# Thermostat.net
KiCad netlist of a schematic drawn in EAGLE
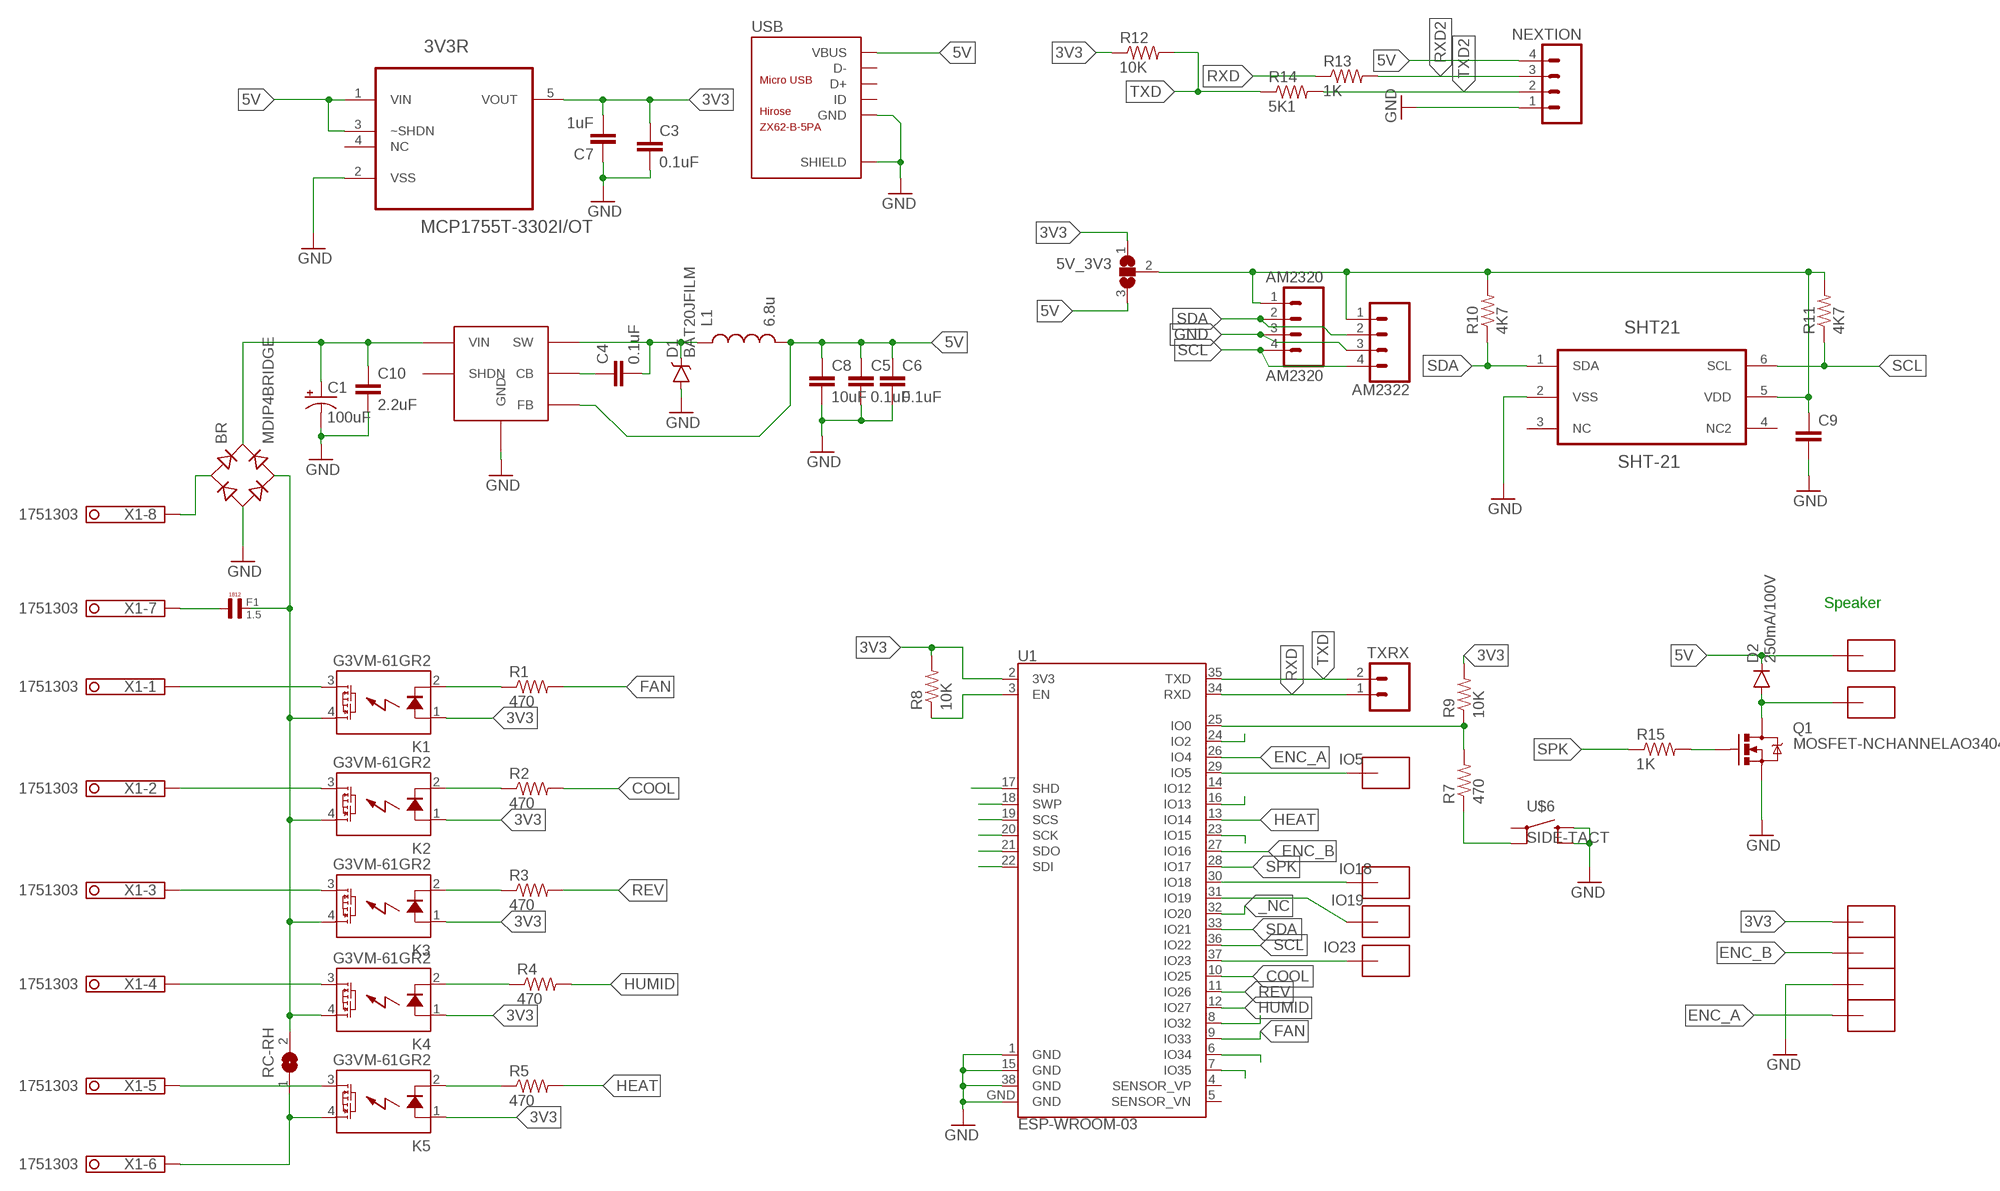
[diagram p0: schematic, sheet 1]

(export (version "E")
  (design (tool "Eeschema 10.0.6"))
  (components
    (comp (ref "3V3R")
      (value "MCP1755T-3302I/OT")
      (footprint "eagle-import:SOT95P270X145-5N")
      (fields (field (name "MPN") "MCP1801T-3302I/OT"))
      (libsource (lib "eagle-import") (part "MCP1801T-3302I/OT"))
    )
    (comp (ref "5V_3V3")
      (value "SJ2W")
      (footprint "eagle-import:SJ_2")
      (libsource (lib "eagle-import") (part "SJ2W"))
    )
    (comp (ref "AM2320")
      (value "AM2320")
      (footprint "eagle-import:1X04")
      (libsource (lib "eagle-import") (part "M04PTH"))
    )
    (comp (ref "AM2322")
      (value "CONN_041.27MM")
      (footprint "eagle-import:1X04_1.27MM")
      (libsource (lib "eagle-import") (part "CONN_041.27MM"))
    )
    (comp (ref "BR")
      (value "MDIP4BRIDGE")
      (footprint "eagle-import:MICRODIP4")
      (libsource (lib "eagle-import") (part "MDIP4BRIDGE"))
    )
    (comp (ref "C1")
      (value "100uF")
      (footprint "eagle-import:PANASONIC_C")
      (libsource (lib "eagle-import") (part "CAP_POLC"))
    )
    (comp (ref "C3")
      (value "0.1uF")
      (footprint "eagle-import:0805")
      (libsource (lib "eagle-import") (part "CAP0805"))
    )
    (comp (ref "C4")
      (value "0.1uF")
      (footprint "eagle-import:0805")
      (libsource (lib "eagle-import") (part "CAP0805"))
    )
    (comp (ref "C5")
      (value "0.1uF")
      (footprint "eagle-import:0805")
      (libsource (lib "eagle-import") (part "CAP0805"))
    )
    (comp (ref "C6")
      (value "0.1uF")
      (footprint "eagle-import:0805")
      (libsource (lib "eagle-import") (part "CAP0805"))
    )
    (comp (ref "C7")
      (value "1uF")
      (footprint "eagle-import:0805")
      (libsource (lib "eagle-import") (part "CAP0805"))
    )
    (comp (ref "C8")
      (value "10uF")
      (footprint "eagle-import:0805")
      (libsource (lib "eagle-import") (part "CAP0805"))
    )
    (comp (ref "C9")
      (value "CAP0603-CAP")
      (footprint "eagle-import:0603-CAP")
      (libsource (lib "eagle-import") (part "CAP0603-CAP"))
    )
    (comp (ref "C10")
      (value "2.2uF")
      (footprint "eagle-import:0805")
      (libsource (lib "eagle-import") (part "CAP0805"))
    )
    (comp (ref "D1")
      (value "BAT20JFILM")
      (footprint "eagle-import:SOD-323")
      (libsource (lib "eagle-import") (part "BAT20JFILM"))
    )
    (comp (ref "D2")
      (value "250mA/100V")
      (footprint "eagle-import:SOD-323")
      (libsource (lib "eagle-import") (part "DIODEBAS16"))
    )
    (comp (ref "F1")
      (value "1.5")
      (footprint "eagle-import:L4,8")
      (libsource (lib "eagle-import") (part "0,1µF"))
    )
    (comp (ref "K1")
      (value "G3VM-61GR2")
      (footprint "eagle-import:SOP04")
      (libsource (lib "eagle-import") (part "AQYSOP22"))
    )
    (comp (ref "K2")
      (value "G3VM-61GR2")
      (footprint "eagle-import:SOP04")
      (libsource (lib "eagle-import") (part "AQYSOP22"))
    )
    (comp (ref "K3")
      (value "G3VM-61GR2")
      (footprint "eagle-import:SOP04")
      (libsource (lib "eagle-import") (part "AQYSOP22"))
    )
    (comp (ref "K4")
      (value "G3VM-61GR2")
      (footprint "eagle-import:SOP04")
      (libsource (lib "eagle-import") (part "AQYSOP22"))
    )
    (comp (ref "K5")
      (value "G3VM-61GR2")
      (footprint "eagle-import:SOP04")
      (libsource (lib "eagle-import") (part "AQYSOP22"))
    )
    (comp (ref "L1")
      (value "6.8u")
      (footprint "eagle-import:1007")
      (libsource (lib "eagle-import") (part "INDUCTOR1007"))
    )
    (comp (ref "NEXTION")
      (value "M04PTH")
      (footprint "eagle-import:1X04")
      (libsource (lib "eagle-import") (part "M04PTH"))
    )
    (comp (ref "Q1")
      (value "MOSFET-NCHANNELAO3404A")
      (footprint "eagle-import:SOT23-3")
      (libsource (lib "eagle-import") (part "MOSFET-NCHANNELAO3404A"))
    )
    (comp (ref "R1")
      (value "470")
      (footprint "eagle-import:0805")
      (libsource (lib "eagle-import") (part "RESISTOR0805-RES"))
    )
    (comp (ref "R2")
      (value "470")
      (footprint "eagle-import:0805")
      (libsource (lib "eagle-import") (part "RESISTOR0805-RES"))
    )
    (comp (ref "R3")
      (value "470")
      (footprint "eagle-import:0805")
      (libsource (lib "eagle-import") (part "RESISTOR0805-RES"))
    )
    (comp (ref "R4")
      (value "470")
      (footprint "eagle-import:0805")
      (libsource (lib "eagle-import") (part "RESISTOR0805-RES"))
    )
    (comp (ref "R5")
      (value "470")
      (footprint "eagle-import:0805")
      (libsource (lib "eagle-import") (part "RESISTOR0805-RES"))
    )
    (comp (ref "R7")
      (value "470")
      (footprint "eagle-import:0805")
      (libsource (lib "eagle-import") (part "SparkFun-Resistors_RESISTOR0805-RES"))
    )
    (comp (ref "R8")
      (value "10K")
      (footprint "eagle-import:0805")
      (libsource (lib "eagle-import") (part "SparkFun-Resistors_RESISTOR0805-RES"))
    )
    (comp (ref "R9")
      (value "10K")
      (footprint "eagle-import:0805")
      (libsource (lib "eagle-import") (part "RESISTOR0805-RES"))
    )
    (comp (ref "R10")
      (value "4K7")
      (footprint "eagle-import:0805")
      (libsource (lib "eagle-import") (part "SparkFun-Resistors_RESISTOR0805-RES"))
    )
    (comp (ref "R11")
      (value "4K7")
      (footprint "eagle-import:0805")
      (libsource (lib "eagle-import") (part "SparkFun-Resistors_RESISTOR0805-RES"))
    )
    (comp (ref "R12")
      (value "10K")
      (footprint "eagle-import:0805")
      (libsource (lib "eagle-import") (part "SparkFun-Resistors_RESISTOR0805-RES"))
    )
    (comp (ref "R13")
      (value "1K")
      (footprint "eagle-import:0805")
      (libsource (lib "eagle-import") (part "SparkFun-Resistors_RESISTOR0805-RES"))
    )
    (comp (ref "R14")
      (value "5K1")
      (footprint "eagle-import:0805")
      (libsource (lib "eagle-import") (part "SparkFun-Resistors_RESISTOR0805-RES"))
    )
    (comp (ref "R15")
      (value "1K")
      (footprint "eagle-import:0805")
      (libsource (lib "eagle-import") (part "SparkFun-Resistors_RESISTOR0805-RES"))
    )
    (comp (ref "RC-RH")
      (value "SJ")
      (footprint "eagle-import:SJ")
      (libsource (lib "eagle-import") (part "SJ"))
    )
    (comp (ref "SHT21")
      (value "SHT-21")
      (footprint "eagle-import:SHT21")
      (libsource (lib "eagle-import") (part "SHT-21"))
    )
    (comp (ref "TXRX")
      (value "M02PTH")
      (footprint "eagle-import:1X02")
      (libsource (lib "eagle-import") (part "M02PTH"))
    )
    (comp (ref "U$1")
      (value "SMD-PAD182X64")
      (footprint "eagle-import:SMD-PAD1")
      (libsource (lib "eagle-import") (part "SMD-PAD182X64"))
    )
    (comp (ref "U$2")
      (value "SMD-PAD182X64")
      (footprint "eagle-import:SMD-PAD1")
      (libsource (lib "eagle-import") (part "SMD-PAD182X64"))
    )
    (comp (ref "U$3")
      (value "SMD-PAD182X64")
      (footprint "eagle-import:SMD-PAD1")
      (libsource (lib "eagle-import") (part "SMD-PAD182X64"))
    )
    (comp (ref "U$4")
      (value "SMD-PAD182X64")
      (footprint "eagle-import:SMD-PAD1")
      (libsource (lib "eagle-import") (part "SMD-PAD182X64"))
    )
    (comp (ref "U$5")
      (value "SMD-PAD1SMD-PAD80X32")
      (footprint "eagle-import:SMD-PAD6")
      (libsource (lib "eagle-import") (part "SMD-PAD1SMD-PAD80X32"))
    )
    (comp (ref "U$6")
      (value "SIDE-TACT")
      (footprint "eagle-import:SIDE-TACT")
      (libsource (lib "eagle-import") (part "SIDE-TACT"))
    )
    (comp (ref "U$7")
      (value "SMD-PAD1SMD-PAD80X32")
      (footprint "eagle-import:SMD-PAD6")
      (libsource (lib "eagle-import") (part "SMD-PAD1SMD-PAD80X32"))
    )
    (comp (ref "U$8")
      (value "SMD-PAD1SMD-PAD80X32")
      (footprint "eagle-import:SMD-PAD6")
      (libsource (lib "eagle-import") (part "SMD-PAD1SMD-PAD80X32"))
    )
    (comp (ref "U$9")
      (value "SMD-PAD1SMD-PAD80X32")
      (footprint "eagle-import:SMD-PAD6")
      (libsource (lib "eagle-import") (part "SMD-PAD1SMD-PAD80X32"))
    )
    (comp (ref "U$10")
      (value "SMD-PAD1SMD-PAD80X32")
      (footprint "eagle-import:SMD-PAD6")
      (libsource (lib "eagle-import") (part "SMD-PAD1SMD-PAD80X32"))
    )
    (comp (ref "U$11")
      (value "SMD-PAD1SMD-PAD80X32")
      (footprint "eagle-import:SMD-PAD6")
      (libsource (lib "eagle-import") (part "SMD-PAD1SMD-PAD80X32"))
    )
    (comp (ref "U1")
      (value "ESP-WROOM-03")
      (footprint "eagle-import:ESP-WROOM-03")
      (libsource (lib "eagle-import") (part "ESP-WROOM-03"))
    )
    (comp (ref "USB")
      (value "ZX62-B-5PA")
      (footprint "eagle-import:MICRO-USB5+6P-SMD-0.65-AB")
      (libsource (lib "eagle-import") (part "MICRO-USB-SMD(ZX62-B-5PA)"))
    )
    (comp (ref "VREG")
      (value "LMR16006YQ")
      (footprint "eagle-import:SOT-23-6")
      (libsource (lib "eagle-import") (part "LMR16006YQ"))
    )
    (comp (ref "X1")
      (value "1751303")
      (footprint "eagle-import:1751303")
      (libsource (lib "eagle-import") (part "1751303"))
    )
  )
  (nets
    (net (code "1") (name "/IO5") (class "Default")
      (node (ref "U$3") (pin ">PAD") (pinfunction "P$1_>PAD") (pintype "bidirectional"))
      (node (ref "U1") (pin "29") (pinfunction "IO5_29") (pintype "bidirectional"))
    )
    (net (code "2") (name "/IO18") (class "Default")
      (node (ref "U$4") (pin ">PAD") (pinfunction "P$1_>PAD") (pintype "bidirectional"))
      (node (ref "U1") (pin "30") (pinfunction "IO18_30") (pintype "bidirectional"))
    )
    (net (code "3") (name "/IO19") (class "Default")
      (node (ref "U$1") (pin ">PAD") (pinfunction "P$1_>PAD") (pintype "bidirectional"))
      (node (ref "U1") (pin "31") (pinfunction "IO19_31") (pintype "bidirectional"))
    )
    (net (code "4") (name "/IO23") (class "Default")
      (node (ref "U$2") (pin ">PAD") (pinfunction "P$1_>PAD") (pintype "bidirectional"))
      (node (ref "U1") (pin "37") (pinfunction "IO23_37") (pintype "bidirectional"))
    )
    (net (code "5") (name "/NC") (class "Default")
      (node (ref "SHT21") (pin "3") (pinfunction "NC_3") (pintype "power_in"))
    )
    (net (code "6") (name "3V3") (class "Default")
      (node (ref "3V3R") (pin "5") (pinfunction "VOUT_5") (pintype "output"))
      (node (ref "5V_3V3") (pin "1") (pinfunction "1_1") (pintype "passive"))
      (node (ref "C3") (pin "1") (pinfunction "1_1") (pintype "passive"))
      (node (ref "C7") (pin "2") (pinfunction "2_2") (pintype "passive"))
      (node (ref "K1") (pin "1") (pinfunction "A_1") (pintype "passive"))
      (node (ref "K2") (pin "1") (pinfunction "A_1") (pintype "passive"))
      (node (ref "K3") (pin "1") (pinfunction "A_1") (pintype "passive"))
      (node (ref "K4") (pin "1") (pinfunction "A_1") (pintype "passive"))
      (node (ref "K5") (pin "1") (pinfunction "A_1") (pintype "passive"))
      (node (ref "R12") (pin "1") (pinfunction "1_1") (pintype "passive"))
      (node (ref "R8") (pin "2") (pinfunction "2_2") (pintype "passive"))
      (node (ref "R9") (pin "2") (pinfunction "2_2") (pintype "passive"))
      (node (ref "U$7") (pin ">PAD") (pinfunction "P$1_>PAD") (pintype "bidirectional"))
      (node (ref "U1") (pin "2") (pinfunction "3V3_2") (pintype "bidirectional"))
    )
    (net (code "7") (name "5V") (class "Default")
      (node (ref "3V3R") (pin "1") (pinfunction "VIN_1") (pintype "power_in"))
      (node (ref "3V3R") (pin "3") (pinfunction "~{SHDN}_3") (pintype "input"))
      (node (ref "5V_3V3") (pin "3") (pinfunction "3_3") (pintype "passive"))
      (node (ref "C5") (pin "1") (pinfunction "1_1") (pintype "passive"))
      (node (ref "C6") (pin "1") (pinfunction "1_1") (pintype "passive"))
      (node (ref "C8") (pin "1") (pinfunction "1_1") (pintype "passive"))
      (node (ref "D2") (pin "C") (pinfunction "C_C") (pintype "passive"))
      (node (ref "L1") (pin "2") (pinfunction "2_2") (pintype "passive"))
      (node (ref "NEXTION") (pin "4") (pinfunction "4_4") (pintype "passive"))
      (node (ref "U$5") (pin ">PAD") (pinfunction "P$1_>PAD") (pintype "bidirectional"))
      (node (ref "USB") (pin "1") (pinfunction "VBUS_1") (pintype "power_in"))
      (node (ref "VREG") (pin "3") (pinfunction "FB_3") (pintype "input"))
    )
    (net (code "8") (name "COOL") (class "Default")
      (node (ref "R2") (pin "2") (pinfunction "2_2") (pintype "passive"))
      (node (ref "U1") (pin "10") (pinfunction "IO25_10") (pintype "bidirectional"))
    )
    (net (code "9") (name "ENC_A") (class "Default")
      (node (ref "U$10") (pin ">PAD") (pinfunction "P$1_>PAD") (pintype "bidirectional"))
      (node (ref "U1") (pin "26") (pinfunction "IO4_26") (pintype "bidirectional"))
    )
    (net (code "10") (name "ENC_B") (class "Default")
      (node (ref "U$8") (pin ">PAD") (pinfunction "P$1_>PAD") (pintype "bidirectional"))
      (node (ref "U1") (pin "27") (pinfunction "IO16_27") (pintype "bidirectional"))
    )
    (net (code "11") (name "FAN") (class "Default")
      (node (ref "R1") (pin "2") (pinfunction "2_2") (pintype "passive"))
      (node (ref "U1") (pin "9") (pinfunction "IO33_9") (pintype "bidirectional"))
    )
    (net (code "12") (name "GND") (class "Default")
      (node (ref "3V3R") (pin "2") (pinfunction "VSS_2") (pintype "passive"))
      (node (ref "AM2320") (pin "3") (pinfunction "3_3") (pintype "passive"))
      (node (ref "AM2322") (pin "3") (pinfunction "3_3") (pintype "passive"))
      (node (ref "BR") (pin "-") (pinfunction "-_-") (pintype "passive"))
      (node (ref "C1") (pin "-") (pinfunction "-_-") (pintype "passive"))
      (node (ref "C10") (pin "2") (pinfunction "2_2") (pintype "passive"))
      (node (ref "C3") (pin "2") (pinfunction "2_2") (pintype "passive"))
      (node (ref "C5") (pin "2") (pinfunction "2_2") (pintype "passive"))
      (node (ref "C6") (pin "2") (pinfunction "2_2") (pintype "passive"))
      (node (ref "C7") (pin "1") (pinfunction "1_1") (pintype "passive"))
      (node (ref "C8") (pin "2") (pinfunction "2_2") (pintype "passive"))
      (node (ref "C9") (pin "2") (pinfunction "2_2") (pintype "passive"))
      (node (ref "D1") (pin "A") (pinfunction "A_A") (pintype "passive"))
      (node (ref "NEXTION") (pin "1") (pinfunction "1_1") (pintype "passive"))
      (node (ref "Q1") (pin "2") (pinfunction "S_2") (pintype "passive"))
      (node (ref "SHT21") (pin "2") (pinfunction "VSS_2") (pintype "input"))
      (node (ref "U$6") (pin "3") (pinfunction "2_3") (pintype "passive"))
      (node (ref "U$6") (pin "4") (pinfunction "4_4") (pintype "passive"))
      (node (ref "U$9") (pin ">PAD") (pinfunction "P$1_>PAD") (pintype "bidirectional"))
      (node (ref "U1") (pin "1") (pinfunction "GND_1") (pintype "bidirectional"))
      (node (ref "U1") (pin "15") (pinfunction "GND_15") (pintype "bidirectional"))
      (node (ref "U1") (pin "38") (pinfunction "GND_38") (pintype "bidirectional"))
      (node (ref "U1") (pin "GND") (pinfunction "GND_GND") (pintype "bidirectional"))
      (node (ref "USB") (pin "5") (pinfunction "GND_5") (pintype "power_in"))
      (node (ref "USB") (pin "P1") (pinfunction "SHIELD_P1") (pintype "power_in"))
      (node (ref "USB") (pin "P2") (pinfunction "SHIELD_P2") (pintype "power_in"))
      (node (ref "USB") (pin "P3") (pinfunction "SHIELD_P3") (pintype "power_in"))
      (node (ref "USB") (pin "P4") (pinfunction "SHIELD_P4") (pintype "power_in"))
      (node (ref "USB") (pin "P5") (pinfunction "SHIELD_P5") (pintype "power_in"))
      (node (ref "USB") (pin "P6") (pinfunction "SHIELD_P6") (pintype "power_in"))
      (node (ref "VREG") (pin "2") (pinfunction "GND_2") (pintype "input"))
    )
    (net (code "13") (name "HEAT") (class "Default")
      (node (ref "R5") (pin "2") (pinfunction "2_2") (pintype "passive"))
      (node (ref "U1") (pin "13") (pinfunction "IO14_13") (pintype "bidirectional"))
    )
    (net (code "14") (name "HUMID") (class "Default")
      (node (ref "R4") (pin "2") (pinfunction "2_2") (pintype "passive"))
      (node (ref "U1") (pin "12") (pinfunction "IO27_12") (pintype "bidirectional"))
    )
    (net (code "15") (name "Net-(F1-1)") (class "Default")
      (node (ref "F1") (pin "P$1") (pinfunction "1_P$1") (pintype "passive"))
      (node (ref "X1") (pin "7") (pinfunction "K_7") (pintype "passive"))
    )
    (net (code "16") (name "Net-(F1-2)") (class "Default")
      (node (ref "BR") (pin "AC2") (pinfunction "AC2_AC2") (pintype "passive"))
      (node (ref "F1") (pin "P$2") (pinfunction "2_P$2") (pintype "passive"))
      (node (ref "K1") (pin "4") (pinfunction "DS1_4") (pintype "passive"))
      (node (ref "K2") (pin "4") (pinfunction "DS1_4") (pintype "passive"))
      (node (ref "K3") (pin "4") (pinfunction "DS1_4") (pintype "passive"))
      (node (ref "K4") (pin "4") (pinfunction "DS1_4") (pintype "passive"))
      (node (ref "RC-RH") (pin "2") (pinfunction "2_2") (pintype "passive"))
    )
    (net (code "17") (name "Net-(K1-DS2)") (class "Default")
      (node (ref "K1") (pin "3") (pinfunction "DS2_3") (pintype "passive"))
      (node (ref "X1") (pin "1") (pinfunction "K_1") (pintype "passive"))
    )
    (net (code "18") (name "Net-(K1-K)") (class "Default")
      (node (ref "K1") (pin "2") (pinfunction "K_2") (pintype "passive"))
      (node (ref "R1") (pin "1") (pinfunction "1_1") (pintype "passive"))
    )
    (net (code "19") (name "Net-(K2-DS2)") (class "Default")
      (node (ref "K2") (pin "3") (pinfunction "DS2_3") (pintype "passive"))
      (node (ref "X1") (pin "2") (pinfunction "K_2") (pintype "passive"))
    )
    (net (code "20") (name "Net-(K2-K)") (class "Default")
      (node (ref "K2") (pin "2") (pinfunction "K_2") (pintype "passive"))
      (node (ref "R2") (pin "1") (pinfunction "1_1") (pintype "passive"))
    )
    (net (code "21") (name "Net-(K3-DS2)") (class "Default")
      (node (ref "K3") (pin "3") (pinfunction "DS2_3") (pintype "passive"))
      (node (ref "X1") (pin "3") (pinfunction "K_3") (pintype "passive"))
    )
    (net (code "22") (name "Net-(K3-K)") (class "Default")
      (node (ref "K3") (pin "2") (pinfunction "K_2") (pintype "passive"))
      (node (ref "R3") (pin "1") (pinfunction "1_1") (pintype "passive"))
    )
    (net (code "23") (name "Net-(K4-DS2)") (class "Default")
      (node (ref "K4") (pin "3") (pinfunction "DS2_3") (pintype "passive"))
      (node (ref "X1") (pin "4") (pinfunction "K_4") (pintype "passive"))
    )
    (net (code "24") (name "Net-(K4-K)") (class "Default")
      (node (ref "K4") (pin "2") (pinfunction "K_2") (pintype "passive"))
      (node (ref "R4") (pin "1") (pinfunction "1_1") (pintype "passive"))
    )
    (net (code "25") (name "Net-(K5-DS1)") (class "Default")
      (node (ref "K5") (pin "4") (pinfunction "DS1_4") (pintype "passive"))
      (node (ref "RC-RH") (pin "1") (pinfunction "1_1") (pintype "passive"))
      (node (ref "X1") (pin "6") (pinfunction "K_6") (pintype "passive"))
    )
    (net (code "26") (name "Net-(K5-DS2)") (class "Default")
      (node (ref "K5") (pin "3") (pinfunction "DS2_3") (pintype "passive"))
      (node (ref "X1") (pin "5") (pinfunction "K_5") (pintype "passive"))
    )
    (net (code "27") (name "Net-(K5-K)") (class "Default")
      (node (ref "K5") (pin "2") (pinfunction "K_2") (pintype "passive"))
      (node (ref "R5") (pin "1") (pinfunction "1_1") (pintype "passive"))
    )
    (net (code "28") (name "Net-(Q1-D)") (class "Default")
      (node (ref "D2") (pin "A") (pinfunction "A_A") (pintype "passive"))
      (node (ref "Q1") (pin "3") (pinfunction "D_3") (pintype "passive"))
      (node (ref "U$11") (pin ">PAD") (pinfunction "P$1_>PAD") (pintype "bidirectional"))
    )
    (net (code "29") (name "Net-(Q1-G)") (class "Default")
      (node (ref "Q1") (pin "1") (pinfunction "G_1") (pintype "passive"))
      (node (ref "R15") (pin "2") (pinfunction "2_2") (pintype "passive"))
    )
    (net (code "30") (name "Net-(SHT21-VDD)") (class "Default")
      (node (ref "5V_3V3") (pin "2") (pinfunction "2_2") (pintype "passive"))
      (node (ref "AM2320") (pin "1") (pinfunction "1_1") (pintype "passive"))
      (node (ref "AM2322") (pin "1") (pinfunction "1_1") (pintype "passive"))
      (node (ref "C9") (pin "1") (pinfunction "1_1") (pintype "passive"))
      (node (ref "R10") (pin "2") (pinfunction "2_2") (pintype "passive"))
      (node (ref "R11") (pin "2") (pinfunction "2_2") (pintype "passive"))
      (node (ref "SHT21") (pin "5") (pinfunction "VDD_5") (pintype "bidirectional"))
    )
    (net (code "31") (name "Net-(U$6-3)") (class "Default")
      (node (ref "R7") (pin "1") (pinfunction "1_1") (pintype "passive"))
      (node (ref "U$6") (pin "2") (pinfunction "3_2") (pintype "passive"))
    )
    (net (code "32") (name "Net-(U1-EN)") (class "Default")
      (node (ref "R8") (pin "1") (pinfunction "1_1") (pintype "passive"))
      (node (ref "U1") (pin "3") (pinfunction "EN_3") (pintype "bidirectional"))
    )
    (net (code "33") (name "Net-(U1-IO0)") (class "Default")
      (node (ref "R7") (pin "2") (pinfunction "2_2") (pintype "passive"))
      (node (ref "R9") (pin "1") (pinfunction "1_1") (pintype "passive"))
      (node (ref "U1") (pin "25") (pinfunction "IO0_25") (pintype "bidirectional"))
    )
    (net (code "34") (name "Net-(VREG-CB)") (class "Default")
      (node (ref "C4") (pin "1") (pinfunction "1_1") (pintype "passive"))
      (node (ref "VREG") (pin "1") (pinfunction "CB_1") (pintype "input"))
    )
    (net (code "35") (name "Net-(VREG-SW)") (class "Default")
      (node (ref "C4") (pin "2") (pinfunction "2_2") (pintype "passive"))
      (node (ref "D1") (pin "C") (pinfunction "C_C") (pintype "passive"))
      (node (ref "L1") (pin "1") (pinfunction "1_1") (pintype "passive"))
      (node (ref "VREG") (pin "6") (pinfunction "SW_6") (pintype "output"))
    )
    (net (code "36") (name "Net-(VREG-VIN)") (class "Default")
      (node (ref "BR") (pin "+") (pinfunction "+_+") (pintype "passive"))
      (node (ref "C1") (pin "+") (pinfunction "+_+") (pintype "passive"))
      (node (ref "C10") (pin "1") (pinfunction "1_1") (pintype "passive"))
      (node (ref "VREG") (pin "5") (pinfunction "VIN_5") (pintype "input"))
    )
    (net (code "37") (name "Net-(X1H-K)") (class "Default")
      (node (ref "BR") (pin "AC1") (pinfunction "AC1_AC1") (pintype "passive"))
      (node (ref "X1") (pin "8") (pinfunction "K_8") (pintype "passive"))
    )
    (net (code "38") (name "REV") (class "Default")
      (node (ref "R3") (pin "2") (pinfunction "2_2") (pintype "passive"))
      (node (ref "U1") (pin "11") (pinfunction "IO26_11") (pintype "bidirectional"))
    )
    (net (code "39") (name "RXD") (class "Default")
      (node (ref "R13") (pin "1") (pinfunction "1_1") (pintype "passive"))
      (node (ref "TXRX") (pin "1") (pinfunction "1_1") (pintype "passive"))
      (node (ref "U1") (pin "34") (pinfunction "RXD_34") (pintype "bidirectional"))
    )
    (net (code "40") (name "RXD2") (class "Default")
      (node (ref "NEXTION") (pin "3") (pinfunction "3_3") (pintype "passive"))
      (node (ref "R13") (pin "2") (pinfunction "2_2") (pintype "passive"))
    )
    (net (code "41") (name "SCL") (class "Default")
      (node (ref "AM2320") (pin "4") (pinfunction "4_4") (pintype "passive"))
      (node (ref "AM2322") (pin "4") (pinfunction "4_4") (pintype "passive"))
      (node (ref "R11") (pin "1") (pinfunction "1_1") (pintype "passive"))
      (node (ref "SHT21") (pin "6") (pinfunction "SCL_6") (pintype "bidirectional"))
      (node (ref "U1") (pin "36") (pinfunction "IO22_36") (pintype "bidirectional"))
    )
    (net (code "42") (name "SDA") (class "Default")
      (node (ref "AM2320") (pin "2") (pinfunction "2_2") (pintype "passive"))
      (node (ref "AM2322") (pin "2") (pinfunction "2_2") (pintype "passive"))
      (node (ref "R10") (pin "1") (pinfunction "1_1") (pintype "passive"))
      (node (ref "SHT21") (pin "1") (pinfunction "SDA_1") (pintype "power_in"))
      (node (ref "U1") (pin "33") (pinfunction "IO21_33") (pintype "bidirectional"))
    )
    (net (code "43") (name "SPK") (class "Default")
      (node (ref "R15") (pin "1") (pinfunction "1_1") (pintype "passive"))
      (node (ref "U1") (pin "28") (pinfunction "IO17_28") (pintype "bidirectional"))
    )
    (net (code "44") (name "TXD") (class "Default")
      (node (ref "R12") (pin "2") (pinfunction "2_2") (pintype "passive"))
      (node (ref "R14") (pin "1") (pinfunction "1_1") (pintype "passive"))
      (node (ref "TXRX") (pin "2") (pinfunction "2_2") (pintype "passive"))
      (node (ref "U1") (pin "35") (pinfunction "TXD_35") (pintype "bidirectional"))
    )
    (net (code "45") (name "TXD2") (class "Default")
      (node (ref "NEXTION") (pin "2") (pinfunction "2_2") (pintype "passive"))
      (node (ref "R14") (pin "2") (pinfunction "2_2") (pintype "passive"))
    )
    (net (code "46") (name "_NC") (class "Default")
      (node (ref "U1") (pin "32") (pinfunction "IO20_32") (pintype "bidirectional"))
    )
    (net (code "47") (name "unconnected-(3V3R-NC-Pad4)") (class "Default")
      (node (ref "3V3R") (pin "4") (pinfunction "NC_4") (pintype "no_connect"))
    )
    (net (code "48") (name "unconnected-(SHT21-NC2-Pad4)") (class "Default")
      (node (ref "SHT21") (pin "4") (pinfunction "NC2_4") (pintype "bidirectional"))
    )
    (net (code "49") (name "unconnected-(U$6-Pad1)") (class "Default")
      (node (ref "U$6") (pin "1") (pinfunction "1_1") (pintype "passive"))
    )
    (net (code "50") (name "unconnected-(U1-IO2-Pad24)") (class "Default")
      (node (ref "U1") (pin "24") (pinfunction "IO2_24") (pintype "bidirectional"))
    )
    (net (code "51") (name "unconnected-(U1-IO12-Pad14)") (class "Default")
      (node (ref "U1") (pin "14") (pinfunction "IO12_14") (pintype "bidirectional"))
    )
    (net (code "52") (name "unconnected-(U1-IO13-Pad16)") (class "Default")
      (node (ref "U1") (pin "16") (pinfunction "IO13_16") (pintype "bidirectional"))
    )
    (net (code "53") (name "unconnected-(U1-IO15-Pad23)") (class "Default")
      (node (ref "U1") (pin "23") (pinfunction "IO15_23") (pintype "bidirectional"))
    )
    (net (code "54") (name "unconnected-(U1-IO32-Pad8)") (class "Default")
      (node (ref "U1") (pin "8") (pinfunction "IO32_8") (pintype "bidirectional"))
    )
    (net (code "55") (name "unconnected-(U1-IO34-Pad6)") (class "Default")
      (node (ref "U1") (pin "6") (pinfunction "IO34_6") (pintype "bidirectional"))
    )
    (net (code "56") (name "unconnected-(U1-IO35-Pad7)") (class "Default")
      (node (ref "U1") (pin "7") (pinfunction "IO35_7") (pintype "bidirectional"))
    )
    (net (code "57") (name "unconnected-(U1-SCK-Pad20)") (class "Default")
      (node (ref "U1") (pin "20") (pinfunction "SCK_20") (pintype "bidirectional"))
    )
    (net (code "58") (name "unconnected-(U1-SCS-Pad19)") (class "Default")
      (node (ref "U1") (pin "19") (pinfunction "SCS_19") (pintype "bidirectional"))
    )
    (net (code "59") (name "unconnected-(U1-SDI-Pad22)") (class "Default")
      (node (ref "U1") (pin "22") (pinfunction "SDI_22") (pintype "bidirectional"))
    )
    (net (code "60") (name "unconnected-(U1-SDO-Pad21)") (class "Default")
      (node (ref "U1") (pin "21") (pinfunction "SDO_21") (pintype "bidirectional"))
    )
    (net (code "61") (name "unconnected-(U1-SENSOR_VN-Pad5)") (class "Default")
      (node (ref "U1") (pin "5") (pinfunction "SENSOR_VN_5") (pintype "bidirectional"))
    )
    (net (code "62") (name "unconnected-(U1-SENSOR_VP-Pad4)") (class "Default")
      (node (ref "U1") (pin "4") (pinfunction "SENSOR_VP_4") (pintype "bidirectional"))
    )
    (net (code "63") (name "unconnected-(U1-SHD-Pad17)") (class "Default")
      (node (ref "U1") (pin "17") (pinfunction "SHD_17") (pintype "bidirectional"))
    )
    (net (code "64") (name "unconnected-(U1-SWP-Pad18)") (class "Default")
      (node (ref "U1") (pin "18") (pinfunction "SWP_18") (pintype "bidirectional"))
    )
    (net (code "65") (name "unconnected-(USB-D+-Pad3)") (class "Default")
      (node (ref "USB") (pin "3") (pinfunction "D+_3") (pintype "bidirectional"))
    )
    (net (code "66") (name "unconnected-(USB-D--Pad2)") (class "Default")
      (node (ref "USB") (pin "2") (pinfunction "D-_2") (pintype "bidirectional"))
    )
    (net (code "67") (name "unconnected-(USB-ID-Pad4)") (class "Default")
      (node (ref "USB") (pin "4") (pinfunction "ID_4") (pintype "bidirectional"))
    )
    (net (code "68") (name "unconnected-(VREG-SHDN-Pad4)") (class "Default")
      (node (ref "VREG") (pin "4") (pinfunction "SHDN_4") (pintype "input"))
    )
  )
)
